# module.net
KiCad netlist of a schematic drawn in EasyEDA
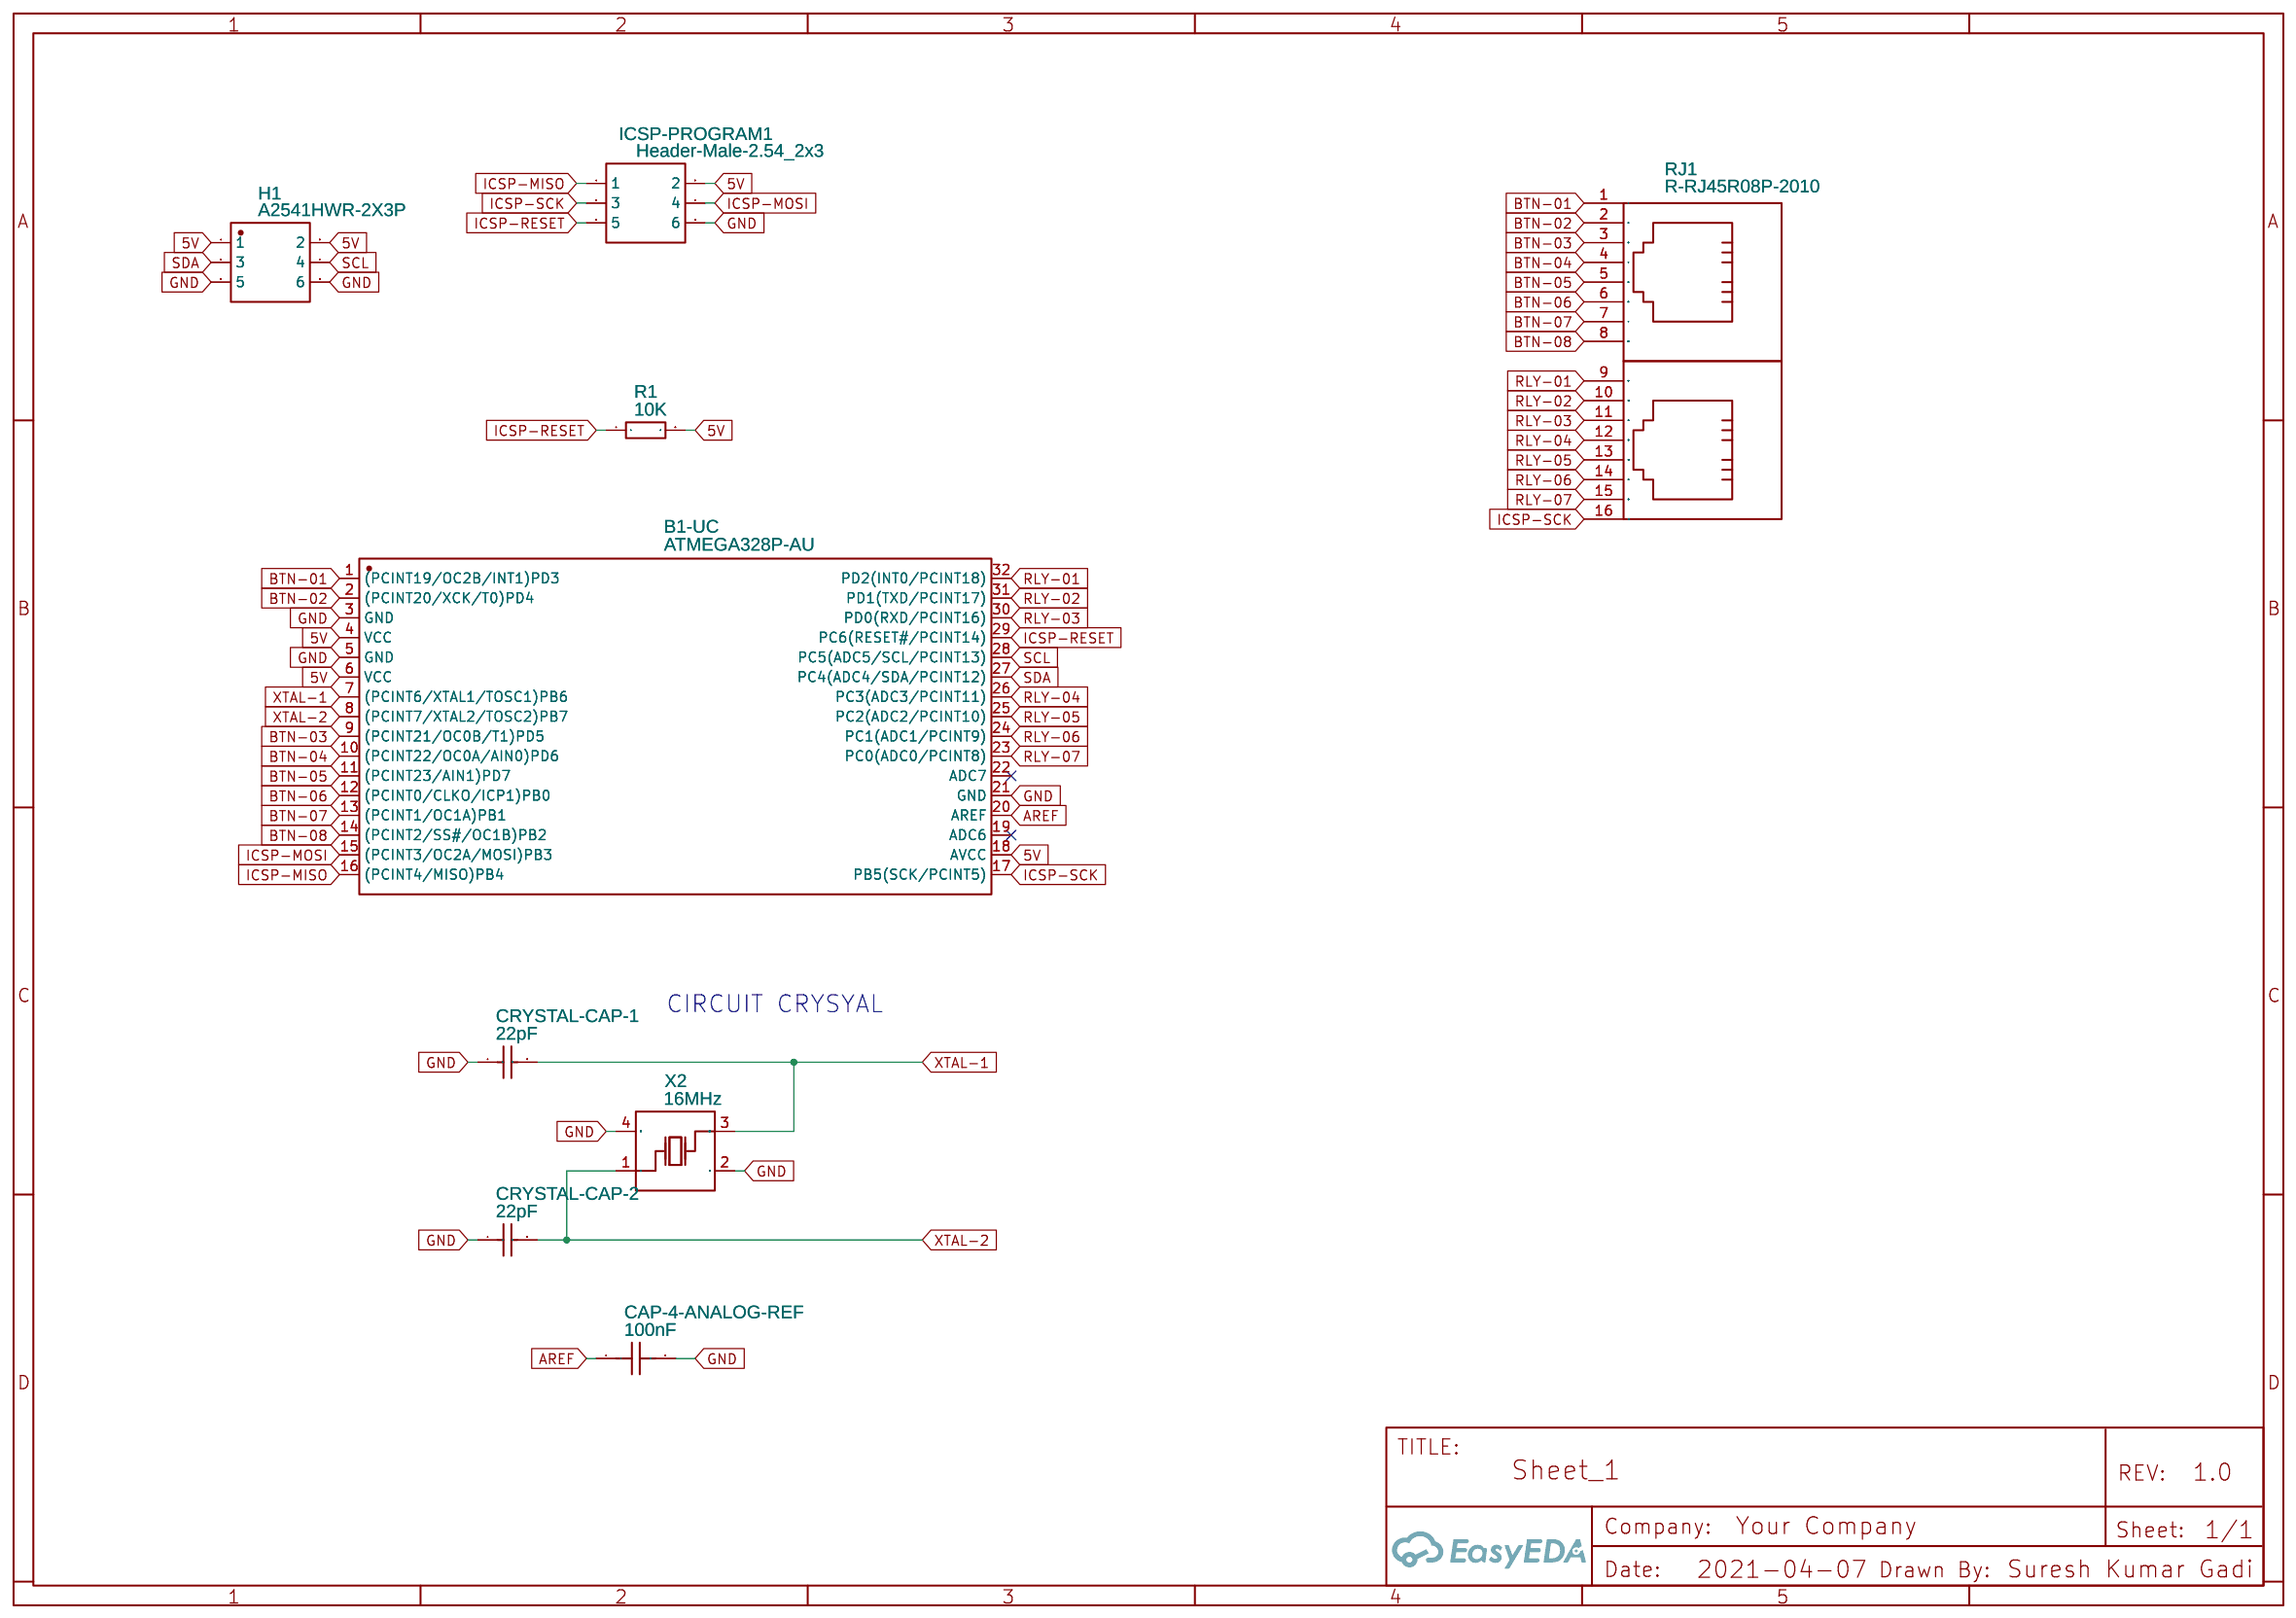
[diagram p0: schematic sheet]

(export (version "E")
  (design (tool "Eeschema 10.0.6"))
  (components
    (comp (ref "B1-UC")
      (value "ATMEGA328P-AU")
      (fields (field (name "BOM_Supplier Part") "C14877"))
      (libsource (lib "") (part "ATMEGA328P-AU"))
    )
    (comp (ref "CAP-4-ANALOG-REF")
      (value "100nF")
      (fields
        (field (name "BOM_Manufacturer Part") "CC0603KRX7R9BB104")
        (field (name "BOM_Supplier Part") "C14663")
      )
      (libsource (lib "") (part "CC0603KRX7R9BB104"))
    )
    (comp (ref "CRYSTAL-CAP-1")
      (value "22pF")
      (fields
        (field (name "BOM_Manufacturer Part") "CL21C220JBANNNC")
        (field (name "BOM_Supplier Part") "C1804")
      )
      (libsource (lib "") (part "CL21C220JBANNNC"))
    )
    (comp (ref "CRYSTAL-CAP-2")
      (value "22pF")
      (fields
        (field (name "BOM_Manufacturer Part") "CL21C220JBANNNC")
        (field (name "BOM_Supplier Part") "C1804")
      )
      (libsource (lib "") (part "CL21C220JBANNNC"))
    )
    (comp (ref "H1")
      (value "A2541HWR-2X3P")
      (fields
        (field (name "BOM_Manufacturer Part") "A2541HWR-2x3P")
        (field (name "BOM_Supplier Part") "C239354")
      )
      (libsource (lib "") (part "A2541HWR-2X3P"))
    )
    (comp (ref "ICSP-PROGRAM1")
      (value "Header-Male-2.54_2x3")
      (fields (field (name "BOM_Supplier Part") "C65114"))
      (libsource (lib "") (part "Header-Male-2.54_2x3"))
    )
    (comp (ref "R1")
      (value "10K")
      (fields
        (field (name "BOM_Manufacturer Part") "1206W4F1002T5E")
        (field (name "BOM_Supplier Part") "C17902")
      )
      (libsource (lib "") (part "1206W4F1002T5E"))
    )
    (comp (ref "RJ1")
      (value "R-RJ45R08P-2010")
      (fields (field (name "BOM_Supplier Part") "C508566"))
      (libsource (lib "") (part "R-RJ45R08P-2010"))
    )
    (comp (ref "X2")
      (value "16MHz")
      (fields
        (field (name "BOM_Manufacturer Part") "X322516MLB4SI")
        (field (name "BOM_Supplier Part") "C13738")
      )
      (libsource (lib "") (part "X322516MLB4SI"))
    )
  )
  (nets
    (net (code "1") (name "5V") (class "Default")
      (node (ref "B1-UC") (pin "18") (pinfunction "AVCC_18") (pintype "unspecified"))
      (node (ref "B1-UC") (pin "4") (pinfunction "VCC_4") (pintype "unspecified"))
      (node (ref "B1-UC") (pin "6") (pinfunction "VCC_6") (pintype "unspecified"))
      (node (ref "H1") (pin "1") (pinfunction "1_1") (pintype "unspecified"))
      (node (ref "H1") (pin "2") (pinfunction "2_2") (pintype "unspecified"))
      (node (ref "ICSP-PROGRAM1") (pin "2") (pinfunction "2_2") (pintype "input"))
      (node (ref "R1") (pin "2") (pinfunction "2_2") (pintype "input"))
    )
    (net (code "2") (name "AREF") (class "Default")
      (node (ref "B1-UC") (pin "20") (pinfunction "AREF_20") (pintype "unspecified"))
      (node (ref "CAP-4-ANALOG-REF") (pin "1") (pinfunction "1_1") (pintype "unspecified"))
    )
    (net (code "3") (name "BTN-01") (class "Default")
      (node (ref "B1-UC") (pin "1") (pinfunction "(PCINT19/OC2B/INT1)PD3_1") (pintype "unspecified"))
      (node (ref "RJ1") (pin "1") (pinfunction "1_1") (pintype "unspecified"))
    )
    (net (code "4") (name "BTN-02") (class "Default")
      (node (ref "B1-UC") (pin "2") (pinfunction "(PCINT20/XCK/T0)PD4_2") (pintype "unspecified"))
      (node (ref "RJ1") (pin "2") (pinfunction "2_2") (pintype "unspecified"))
    )
    (net (code "5") (name "BTN-03") (class "Default")
      (node (ref "B1-UC") (pin "9") (pinfunction "(PCINT21/OC0B/T1)PD5_9") (pintype "unspecified"))
      (node (ref "RJ1") (pin "3") (pinfunction "3_3") (pintype "unspecified"))
    )
    (net (code "6") (name "BTN-04") (class "Default")
      (node (ref "B1-UC") (pin "10") (pinfunction "(PCINT22/OC0A/AIN0)PD6_10") (pintype "unspecified"))
      (node (ref "RJ1") (pin "4") (pinfunction "4_4") (pintype "unspecified"))
    )
    (net (code "7") (name "BTN-05") (class "Default")
      (node (ref "B1-UC") (pin "11") (pinfunction "(PCINT23/AIN1)PD7_11") (pintype "unspecified"))
      (node (ref "RJ1") (pin "5") (pinfunction "5_5") (pintype "unspecified"))
    )
    (net (code "8") (name "BTN-06") (class "Default")
      (node (ref "B1-UC") (pin "12") (pinfunction "(PCINT0/CLKO/ICP1)PB0_12") (pintype "unspecified"))
      (node (ref "RJ1") (pin "6") (pinfunction "6_6") (pintype "unspecified"))
    )
    (net (code "9") (name "BTN-07") (class "Default")
      (node (ref "B1-UC") (pin "13") (pinfunction "(PCINT1/OC1A)PB1_13") (pintype "unspecified"))
      (node (ref "RJ1") (pin "7") (pinfunction "7_7") (pintype "unspecified"))
    )
    (net (code "10") (name "BTN-08") (class "Default")
      (node (ref "B1-UC") (pin "14") (pinfunction "(PCINT2/SS#/OC1B)PB2_14") (pintype "unspecified"))
      (node (ref "RJ1") (pin "8") (pinfunction "8_8") (pintype "unspecified"))
    )
    (net (code "11") (name "GND") (class "Default")
      (node (ref "B1-UC") (pin "21") (pinfunction "GND_21") (pintype "unspecified"))
      (node (ref "B1-UC") (pin "3") (pinfunction "GND_3") (pintype "unspecified"))
      (node (ref "B1-UC") (pin "5") (pinfunction "GND_5") (pintype "unspecified"))
      (node (ref "CAP-4-ANALOG-REF") (pin "2") (pinfunction "2_2") (pintype "unspecified"))
      (node (ref "CRYSTAL-CAP-1") (pin "1") (pinfunction "1_1") (pintype "input"))
      (node (ref "CRYSTAL-CAP-2") (pin "1") (pinfunction "1_1") (pintype "input"))
      (node (ref "H1") (pin "5") (pinfunction "5_5") (pintype "unspecified"))
      (node (ref "H1") (pin "6") (pinfunction "6_6") (pintype "unspecified"))
      (node (ref "ICSP-PROGRAM1") (pin "6") (pinfunction "6_6") (pintype "input"))
      (node (ref "X2") (pin "2") (pinfunction "GND_2") (pintype "unspecified"))
      (node (ref "X2") (pin "4") (pinfunction "GND_4") (pintype "unspecified"))
    )
    (net (code "12") (name "ICSP-MISO") (class "Default")
      (node (ref "B1-UC") (pin "16") (pinfunction "(PCINT4/MISO)PB4_16") (pintype "unspecified"))
      (node (ref "ICSP-PROGRAM1") (pin "1") (pinfunction "1_1") (pintype "input"))
    )
    (net (code "13") (name "ICSP-MOSI") (class "Default")
      (node (ref "B1-UC") (pin "15") (pinfunction "(PCINT3/OC2A/MOSI)PB3_15") (pintype "unspecified"))
      (node (ref "ICSP-PROGRAM1") (pin "4") (pinfunction "4_4") (pintype "input"))
    )
    (net (code "14") (name "ICSP-RESET") (class "Default")
      (node (ref "B1-UC") (pin "29") (pinfunction "PC6(RESET#/PCINT14)_29") (pintype "unspecified"))
      (node (ref "ICSP-PROGRAM1") (pin "5") (pinfunction "5_5") (pintype "input"))
      (node (ref "R1") (pin "1") (pinfunction "1_1") (pintype "input"))
    )
    (net (code "15") (name "ICSP-SCK") (class "Default")
      (node (ref "B1-UC") (pin "17") (pinfunction "PB5(SCK/PCINT5)_17") (pintype "unspecified"))
      (node (ref "ICSP-PROGRAM1") (pin "3") (pinfunction "3_3") (pintype "input"))
      (node (ref "RJ1") (pin "16") (pinfunction "16_16") (pintype "unspecified"))
    )
    (net (code "16") (name "RLY-01") (class "Default")
      (node (ref "B1-UC") (pin "32") (pinfunction "PD2(INT0/PCINT18)_32") (pintype "unspecified"))
      (node (ref "RJ1") (pin "9") (pinfunction "9_9") (pintype "unspecified"))
    )
    (net (code "17") (name "RLY-02") (class "Default")
      (node (ref "B1-UC") (pin "31") (pinfunction "PD1(TXD/PCINT17)_31") (pintype "unspecified"))
      (node (ref "RJ1") (pin "10") (pinfunction "10_10") (pintype "unspecified"))
    )
    (net (code "18") (name "RLY-03") (class "Default")
      (node (ref "B1-UC") (pin "30") (pinfunction "PD0(RXD/PCINT16)_30") (pintype "unspecified"))
      (node (ref "RJ1") (pin "11") (pinfunction "11_11") (pintype "unspecified"))
    )
    (net (code "19") (name "RLY-04") (class "Default")
      (node (ref "B1-UC") (pin "26") (pinfunction "PC3(ADC3/PCINT11)_26") (pintype "unspecified"))
      (node (ref "RJ1") (pin "12") (pinfunction "12_12") (pintype "unspecified"))
    )
    (net (code "20") (name "RLY-05") (class "Default")
      (node (ref "B1-UC") (pin "25") (pinfunction "PC2(ADC2/PCINT10)_25") (pintype "unspecified"))
      (node (ref "RJ1") (pin "13") (pinfunction "13_13") (pintype "unspecified"))
    )
    (net (code "21") (name "RLY-06") (class "Default")
      (node (ref "B1-UC") (pin "24") (pinfunction "PC1(ADC1/PCINT9)_24") (pintype "unspecified"))
      (node (ref "RJ1") (pin "14") (pinfunction "14_14") (pintype "unspecified"))
    )
    (net (code "22") (name "RLY-07") (class "Default")
      (node (ref "B1-UC") (pin "23") (pinfunction "PC0(ADC0/PCINT8)_23") (pintype "unspecified"))
      (node (ref "RJ1") (pin "15") (pinfunction "15_15") (pintype "unspecified"))
    )
    (net (code "23") (name "SCL") (class "Default")
      (node (ref "B1-UC") (pin "28") (pinfunction "PC5(ADC5/SCL/PCINT13)_28") (pintype "unspecified"))
      (node (ref "H1") (pin "4") (pinfunction "4_4") (pintype "unspecified"))
    )
    (net (code "24") (name "SDA") (class "Default")
      (node (ref "B1-UC") (pin "27") (pinfunction "PC4(ADC4/SDA/PCINT12)_27") (pintype "unspecified"))
      (node (ref "H1") (pin "3") (pinfunction "3_3") (pintype "unspecified"))
    )
    (net (code "25") (name "XTAL-1") (class "Default")
      (node (ref "B1-UC") (pin "7") (pinfunction "(PCINT6/XTAL1/TOSC1)PB6_7") (pintype "unspecified"))
      (node (ref "CRYSTAL-CAP-1") (pin "2") (pinfunction "2_2") (pintype "input"))
      (node (ref "X2") (pin "3") (pinfunction "OSC2_3") (pintype "unspecified"))
    )
    (net (code "26") (name "XTAL-2") (class "Default")
      (node (ref "B1-UC") (pin "8") (pinfunction "(PCINT7/XTAL2/TOSC2)PB7_8") (pintype "unspecified"))
      (node (ref "CRYSTAL-CAP-2") (pin "2") (pinfunction "2_2") (pintype "input"))
      (node (ref "X2") (pin "1") (pinfunction "OSC1_1") (pintype "unspecified"))
    )
    (net (code "27") (name "unconnected-(B1-UC-ADC6-Pad19)") (class "Default")
      (node (ref "B1-UC") (pin "19") (pinfunction "ADC6_19") (pintype "unspecified+no_connect"))
    )
    (net (code "28") (name "unconnected-(B1-UC-ADC7-Pad22)") (class "Default")
      (node (ref "B1-UC") (pin "22") (pinfunction "ADC7_22") (pintype "unspecified+no_connect"))
    )
  )
)
